# Hall_Sensor.net
KiCad netlist of a schematic drawn in EAGLE
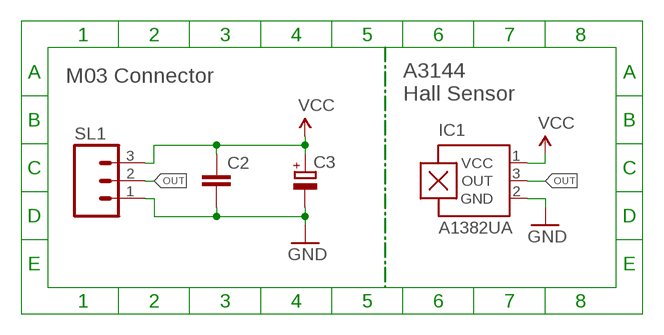
[diagram p0: schematic, sheet 1]

(export (version "E")
  (design (tool "Eeschema 10.0.6"))
  (components
    (comp (ref "C2")
      (value "C-EU025-025X050")
      (footprint "eagle-import:C025-025X050")
      (libsource (lib "eagle-import") (part "C-EU025-025X050"))
    )
    (comp (ref "C3")
      (value "CPOL-EUE2,5-6E")
      (footprint "eagle-import:E2,5-6E")
      (libsource (lib "eagle-import") (part "CPOL-EUE2,5-6E"))
    )
    (comp (ref "IC1")
      (value "A1382UA")
      (footprint "eagle-import:SIP3-UA")
      (fields (field (name "MPN") "A1382LUA-T"))
      (libsource (lib "eagle-import") (part "A13?UA82"))
    )
    (comp (ref "SL1")
      (value "M03")
      (footprint "eagle-import:03P")
      (libsource (lib "eagle-import") (part "M03"))
    )
  )
  (nets
    (net (code "1") (name "GND") (class "Default")
      (node (ref "C2") (pin "2") (pinfunction "2_2") (pintype "passive"))
      (node (ref "C3") (pin "-") (pinfunction "-_-") (pintype "passive"))
      (node (ref "IC1") (pin "2") (pinfunction "GND_2") (pintype "power_in"))
      (node (ref "SL1") (pin "1") (pinfunction "1_1") (pintype "passive"))
    )
    (net (code "2") (name "OUT") (class "Default")
      (node (ref "IC1") (pin "3") (pinfunction "OUT_3") (pintype "output"))
      (node (ref "SL1") (pin "2") (pinfunction "2_2") (pintype "passive"))
    )
    (net (code "3") (name "VCC") (class "Default")
      (node (ref "C2") (pin "1") (pinfunction "1_1") (pintype "passive"))
      (node (ref "C3") (pin "+") (pinfunction "+_+") (pintype "passive"))
      (node (ref "IC1") (pin "1") (pinfunction "VCC_1") (pintype "power_in"))
      (node (ref "SL1") (pin "3") (pinfunction "3_3") (pintype "passive"))
    )
  )
)
